# Sonar_Power_Schematic.net
KiCad netlist of a schematic drawn in EAGLE
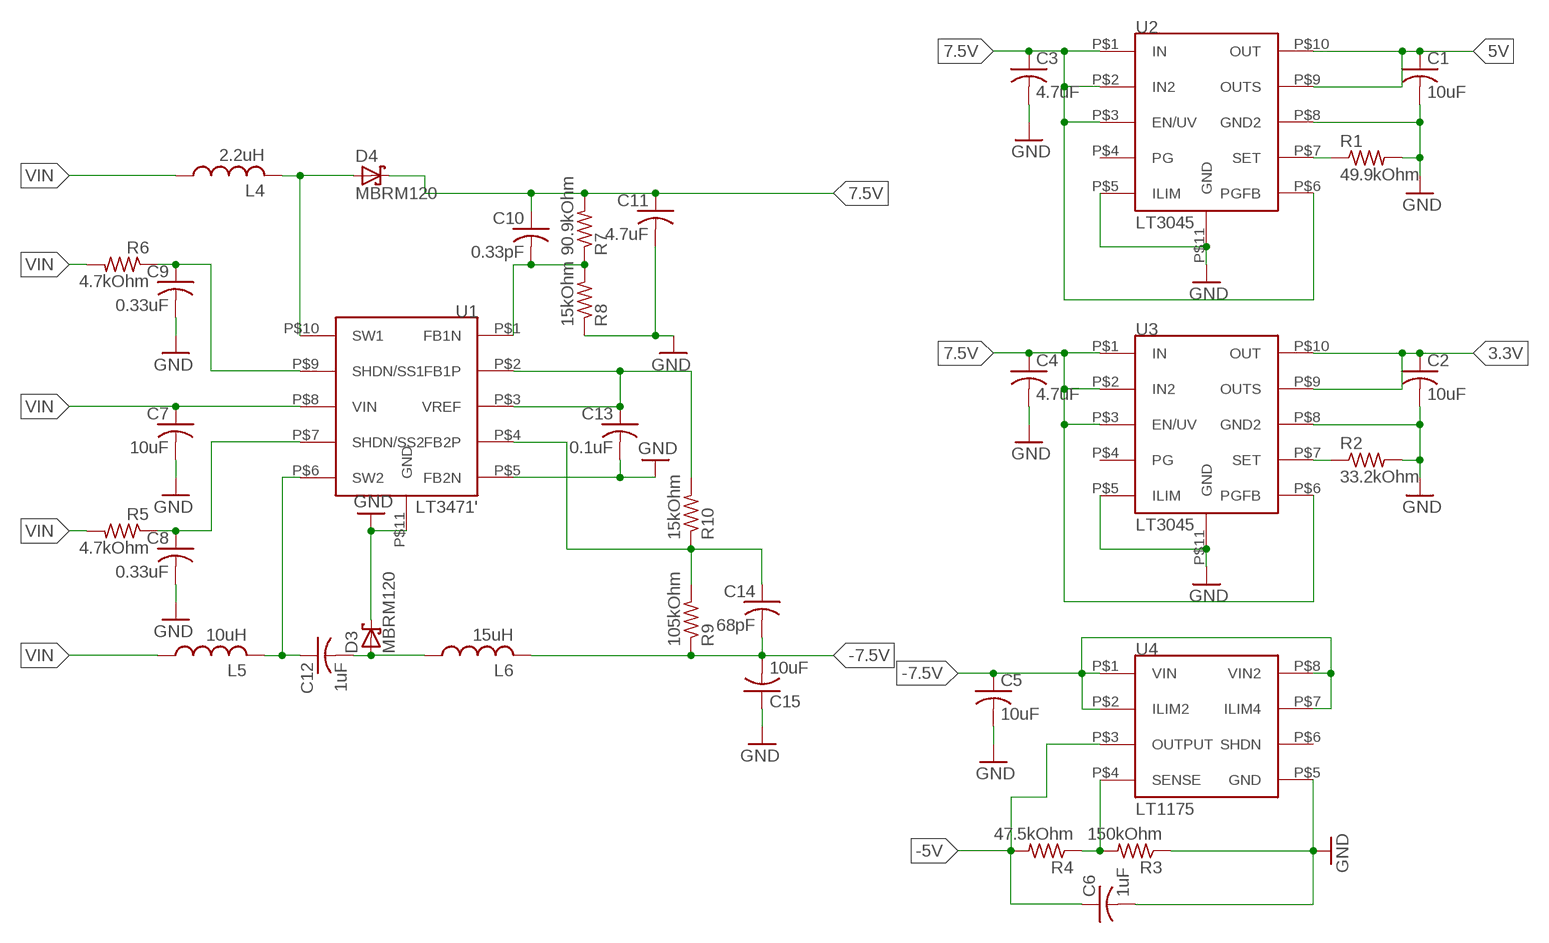
[diagram p0: schematic, sheet 1]

(export (version "E")
  (design (tool "Eeschema 10.0.6"))
  (components
    (comp (ref "C1")
      (value "10uF")
      (footprint "eagle-import:C1206K")
      (libsource (lib "eagle-import") (part "C-USC1206K"))
    )
    (comp (ref "C2")
      (value "10uF")
      (footprint "eagle-import:C1206K")
      (libsource (lib "eagle-import") (part "C-USC1206K"))
    )
    (comp (ref "C3")
      (value "4.7uF")
      (footprint "eagle-import:C0603")
      (libsource (lib "eagle-import") (part "C-USC0603"))
    )
    (comp (ref "C4")
      (value "4.7uF")
      (footprint "eagle-import:C0603")
      (libsource (lib "eagle-import") (part "C-USC0603"))
    )
    (comp (ref "C5")
      (value "10uF")
      (footprint "eagle-import:C0603")
      (libsource (lib "eagle-import") (part "C-USC0603"))
    )
    (comp (ref "C6")
      (value "1uF")
      (footprint "eagle-import:C0603")
      (libsource (lib "eagle-import") (part "C-USC0603"))
    )
    (comp (ref "C7")
      (value "10uF")
      (footprint "eagle-import:C0603")
      (libsource (lib "eagle-import") (part "C-USC0603"))
    )
    (comp (ref "C8")
      (value "0.33uF")
      (footprint "eagle-import:C0603")
      (libsource (lib "eagle-import") (part "C-USC0603"))
    )
    (comp (ref "C9")
      (value "0.33uF")
      (footprint "eagle-import:C0603")
      (libsource (lib "eagle-import") (part "C-USC0603"))
    )
    (comp (ref "C10")
      (value "0.33pF")
      (footprint "eagle-import:C0603")
      (libsource (lib "eagle-import") (part "C-USC0603"))
    )
    (comp (ref "C11")
      (value "4.7uF")
      (footprint "eagle-import:C0603")
      (libsource (lib "eagle-import") (part "C-USC0603"))
    )
    (comp (ref "C12")
      (value "1uF")
      (footprint "eagle-import:C0603")
      (libsource (lib "eagle-import") (part "C-USC0603"))
    )
    (comp (ref "C13")
      (value "0.1uF")
      (footprint "eagle-import:C0603")
      (libsource (lib "eagle-import") (part "C-USC0603"))
    )
    (comp (ref "C14")
      (value "68pF")
      (footprint "eagle-import:C0603")
      (libsource (lib "eagle-import") (part "C-USC0603"))
    )
    (comp (ref "C15")
      (value "10uF")
      (footprint "eagle-import:C0603")
      (libsource (lib "eagle-import") (part "C-USC0603"))
    )
    (comp (ref "D3")
      (value "MBRM120")
      (footprint "eagle-import:DO-216AA")
      (libsource (lib "eagle-import") (part "MBRM120"))
    )
    (comp (ref "D4")
      (value "MBRM120")
      (footprint "eagle-import:DO-216AA")
      (libsource (lib "eagle-import") (part "MBRM120"))
    )
    (comp (ref "L4")
      (value "2.2uH")
      (footprint "eagle-import:NS4.9X4.9")
      (libsource (lib "eagle-import") (part "LQH5BPN2R2N38L"))
    )
    (comp (ref "L5")
      (value "10uH")
      (footprint "eagle-import:NS5X5")
      (libsource (lib "eagle-import") (part "VLS5045EX-100M2"))
    )
    (comp (ref "L6")
      (value "15uH")
      (footprint "eagle-import:NS5X5")
      (libsource (lib "eagle-import") (part "VLS5045EX-150M-CA1"))
    )
    (comp (ref "R1")
      (value "49.9kOhm")
      (footprint "eagle-import:R0603")
      (libsource (lib "eagle-import") (part "R-US_R0603"))
    )
    (comp (ref "R2")
      (value "33.2kOhm")
      (footprint "eagle-import:R0603")
      (libsource (lib "eagle-import") (part "R-US_R0603"))
    )
    (comp (ref "R3")
      (value "150kOhm")
      (footprint "eagle-import:R0603")
      (libsource (lib "eagle-import") (part "R-US_R0603"))
    )
    (comp (ref "R4")
      (value "47.5kOhm")
      (footprint "eagle-import:R0603")
      (libsource (lib "eagle-import") (part "R-US_R0603"))
    )
    (comp (ref "R5")
      (value "4.7kOhm")
      (footprint "eagle-import:R0603")
      (libsource (lib "eagle-import") (part "R-US_R0603"))
    )
    (comp (ref "R6")
      (value "4.7kOhm")
      (footprint "eagle-import:R0603")
      (libsource (lib "eagle-import") (part "R-US_R0603"))
    )
    (comp (ref "R7")
      (value "90.9kOhm")
      (footprint "eagle-import:R0603")
      (libsource (lib "eagle-import") (part "R-US_R0603"))
    )
    (comp (ref "R8")
      (value "15kOhm")
      (footprint "eagle-import:R0603")
      (libsource (lib "eagle-import") (part "R-US_R0603"))
    )
    (comp (ref "R9")
      (value "105kOhm")
      (footprint "eagle-import:R0603")
      (libsource (lib "eagle-import") (part "R-US_R0603"))
    )
    (comp (ref "R10")
      (value "15kOhm")
      (footprint "eagle-import:R0603")
      (libsource (lib "eagle-import") (part "R-US_R0603"))
    )
    (comp (ref "U1")
      (value "LT3471'")
      (footprint "eagle-import:10-WFDFN")
      (libsource (lib "eagle-import") (part "LT3471'"))
    )
    (comp (ref "U2")
      (value "LT3045")
      (footprint "eagle-import:10-WFDFN")
      (libsource (lib "eagle-import") (part "LT3045"))
    )
    (comp (ref "U3")
      (value "LT3045")
      (footprint "eagle-import:10-WFDFN")
      (libsource (lib "eagle-import") (part "LT3045"))
    )
    (comp (ref "U4")
      (value "LT1175")
      (footprint "eagle-import:8-SOIC")
      (libsource (lib "eagle-import") (part "LT1175"))
    )
  )
  (nets
    (net (code "1") (name "-5V") (class "Default")
      (node (ref "C6") (pin "1") (pinfunction "1_1") (pintype "passive"))
      (node (ref "R4") (pin "2") (pinfunction "2_2") (pintype "passive"))
      (node (ref "U4") (pin "P$3") (pinfunction "OUTPUT_P$3") (pintype "bidirectional"))
    )
    (net (code "2") (name "-7.5V") (class "Default")
      (node (ref "C14") (pin "2") (pinfunction "2_2") (pintype "passive"))
      (node (ref "C15") (pin "2") (pinfunction "2_2") (pintype "passive"))
      (node (ref "C5") (pin "1") (pinfunction "1_1") (pintype "passive"))
      (node (ref "L6") (pin "P$2") (pinfunction "2_P$2") (pintype "passive"))
      (node (ref "R9") (pin "1") (pinfunction "1_1") (pintype "passive"))
      (node (ref "U4") (pin "P$1") (pinfunction "VIN_P$1") (pintype "power_in"))
      (node (ref "U4") (pin "P$2") (pinfunction "ILIM2_P$2") (pintype "bidirectional"))
      (node (ref "U4") (pin "P$7") (pinfunction "ILIM4_P$7") (pintype "bidirectional"))
      (node (ref "U4") (pin "P$8") (pinfunction "VIN2_P$8") (pintype "power_in"))
    )
    (net (code "3") (name "3.3V") (class "Default")
      (node (ref "C2") (pin "1") (pinfunction "1_1") (pintype "passive"))
      (node (ref "U3") (pin "P$10") (pinfunction "OUT_P$10") (pintype "bidirectional"))
      (node (ref "U3") (pin "P$9") (pinfunction "OUTS_P$9") (pintype "bidirectional"))
    )
    (net (code "4") (name "5V") (class "Default")
      (node (ref "C1") (pin "1") (pinfunction "1_1") (pintype "passive"))
      (node (ref "U2") (pin "P$10") (pinfunction "OUT_P$10") (pintype "bidirectional"))
      (node (ref "U2") (pin "P$9") (pinfunction "OUTS_P$9") (pintype "bidirectional"))
    )
    (net (code "5") (name "7.5V") (class "Default")
      (node (ref "C10") (pin "1") (pinfunction "1_1") (pintype "passive"))
      (node (ref "C11") (pin "1") (pinfunction "1_1") (pintype "passive"))
      (node (ref "C3") (pin "1") (pinfunction "1_1") (pintype "passive"))
      (node (ref "C4") (pin "1") (pinfunction "1_1") (pintype "passive"))
      (node (ref "D4") (pin "P$1") (pinfunction "C_P$1") (pintype "passive"))
      (node (ref "R7") (pin "2") (pinfunction "2_2") (pintype "passive"))
      (node (ref "U2") (pin "P$1") (pinfunction "IN_P$1") (pintype "power_in"))
      (node (ref "U2") (pin "P$2") (pinfunction "IN2_P$2") (pintype "power_in"))
      (node (ref "U2") (pin "P$3") (pinfunction "EN/UV_P$3") (pintype "bidirectional"))
      (node (ref "U2") (pin "P$6") (pinfunction "PGFB_P$6") (pintype "bidirectional"))
      (node (ref "U3") (pin "P$1") (pinfunction "IN_P$1") (pintype "power_in"))
      (node (ref "U3") (pin "P$2") (pinfunction "IN2_P$2") (pintype "power_in"))
      (node (ref "U3") (pin "P$3") (pinfunction "EN/UV_P$3") (pintype "bidirectional"))
      (node (ref "U3") (pin "P$6") (pinfunction "PGFB_P$6") (pintype "bidirectional"))
    )
    (net (code "6") (name "GND") (class "Default")
      (node (ref "C1") (pin "2") (pinfunction "2_2") (pintype "passive"))
      (node (ref "C11") (pin "2") (pinfunction "2_2") (pintype "passive"))
      (node (ref "C13") (pin "2") (pinfunction "2_2") (pintype "passive"))
      (node (ref "C15") (pin "1") (pinfunction "1_1") (pintype "passive"))
      (node (ref "C2") (pin "2") (pinfunction "2_2") (pintype "passive"))
      (node (ref "C3") (pin "2") (pinfunction "2_2") (pintype "passive"))
      (node (ref "C4") (pin "2") (pinfunction "2_2") (pintype "passive"))
      (node (ref "C5") (pin "2") (pinfunction "2_2") (pintype "passive"))
      (node (ref "C6") (pin "2") (pinfunction "2_2") (pintype "passive"))
      (node (ref "C7") (pin "2") (pinfunction "2_2") (pintype "passive"))
      (node (ref "C8") (pin "2") (pinfunction "2_2") (pintype "passive"))
      (node (ref "C9") (pin "2") (pinfunction "2_2") (pintype "passive"))
      (node (ref "D3") (pin "P$1") (pinfunction "C_P$1") (pintype "passive"))
      (node (ref "R1") (pin "2") (pinfunction "2_2") (pintype "passive"))
      (node (ref "R2") (pin "2") (pinfunction "2_2") (pintype "passive"))
      (node (ref "R3") (pin "1") (pinfunction "1_1") (pintype "passive"))
      (node (ref "R8") (pin "1") (pinfunction "1_1") (pintype "passive"))
      (node (ref "U1") (pin "P$11") (pinfunction "GND_P$11") (pintype "power_in"))
      (node (ref "U1") (pin "P$5") (pinfunction "FB2N_P$5") (pintype "bidirectional"))
      (node (ref "U2") (pin "P$11") (pinfunction "GND_P$11") (pintype "power_in"))
      (node (ref "U2") (pin "P$5") (pinfunction "ILIM_P$5") (pintype "bidirectional"))
      (node (ref "U2") (pin "P$8") (pinfunction "GND2_P$8") (pintype "power_in"))
      (node (ref "U3") (pin "P$11") (pinfunction "GND_P$11") (pintype "power_in"))
      (node (ref "U3") (pin "P$5") (pinfunction "ILIM_P$5") (pintype "bidirectional"))
      (node (ref "U3") (pin "P$8") (pinfunction "GND2_P$8") (pintype "power_in"))
      (node (ref "U4") (pin "P$5") (pinfunction "GND_P$5") (pintype "power_in"))
    )
    (net (code "7") (name "Net-(D3-A)") (class "Default")
      (node (ref "C12") (pin "2") (pinfunction "2_2") (pintype "passive"))
      (node (ref "D3") (pin "P$2") (pinfunction "A_P$2") (pintype "passive"))
      (node (ref "L6") (pin "P$1") (pinfunction "1_P$1") (pintype "passive"))
    )
    (net (code "8") (name "Net-(D4-A)") (class "Default")
      (node (ref "D4") (pin "P$2") (pinfunction "A_P$2") (pintype "passive"))
      (node (ref "L4") (pin "P$2") (pinfunction "2_P$2") (pintype "passive"))
      (node (ref "U1") (pin "P$10") (pinfunction "SW1_P$10") (pintype "bidirectional"))
    )
    (net (code "9") (name "Net-(L5-2)") (class "Default")
      (node (ref "C12") (pin "1") (pinfunction "1_1") (pintype "passive"))
      (node (ref "L5") (pin "P$2") (pinfunction "2_P$2") (pintype "passive"))
      (node (ref "U1") (pin "P$6") (pinfunction "SW2_P$6") (pintype "bidirectional"))
    )
    (net (code "10") (name "Net-(U1-FB1N)") (class "Default")
      (node (ref "C10") (pin "2") (pinfunction "2_2") (pintype "passive"))
      (node (ref "R7") (pin "1") (pinfunction "1_1") (pintype "passive"))
      (node (ref "R8") (pin "2") (pinfunction "2_2") (pintype "passive"))
      (node (ref "U1") (pin "P$1") (pinfunction "FB1N_P$1") (pintype "bidirectional"))
    )
    (net (code "11") (name "Net-(U1-FB1P)") (class "Default")
      (node (ref "C13") (pin "1") (pinfunction "1_1") (pintype "passive"))
      (node (ref "R10") (pin "2") (pinfunction "2_2") (pintype "passive"))
      (node (ref "U1") (pin "P$2") (pinfunction "FB1P_P$2") (pintype "bidirectional"))
      (node (ref "U1") (pin "P$3") (pinfunction "VREF_P$3") (pintype "power_in"))
    )
    (net (code "12") (name "Net-(U1-FB2P)") (class "Default")
      (node (ref "C14") (pin "1") (pinfunction "1_1") (pintype "passive"))
      (node (ref "R10") (pin "1") (pinfunction "1_1") (pintype "passive"))
      (node (ref "R9") (pin "2") (pinfunction "2_2") (pintype "passive"))
      (node (ref "U1") (pin "P$4") (pinfunction "FB2P_P$4") (pintype "bidirectional"))
    )
    (net (code "13") (name "Net-(U1-SHDN{slash}SS1)") (class "Default")
      (node (ref "C9") (pin "1") (pinfunction "1_1") (pintype "passive"))
      (node (ref "R6") (pin "1") (pinfunction "1_1") (pintype "passive"))
      (node (ref "U1") (pin "P$9") (pinfunction "SHDN/SS1_P$9") (pintype "bidirectional"))
    )
    (net (code "14") (name "Net-(U1-SHDN{slash}SS2)") (class "Default")
      (node (ref "C8") (pin "1") (pinfunction "1_1") (pintype "passive"))
      (node (ref "R5") (pin "1") (pinfunction "1_1") (pintype "passive"))
      (node (ref "U1") (pin "P$7") (pinfunction "SHDN/SS2_P$7") (pintype "bidirectional"))
    )
    (net (code "15") (name "Net-(U2-SET)") (class "Default")
      (node (ref "R1") (pin "1") (pinfunction "1_1") (pintype "passive"))
      (node (ref "U2") (pin "P$7") (pinfunction "SET_P$7") (pintype "bidirectional"))
    )
    (net (code "16") (name "Net-(U3-SET)") (class "Default")
      (node (ref "R2") (pin "1") (pinfunction "1_1") (pintype "passive"))
      (node (ref "U3") (pin "P$7") (pinfunction "SET_P$7") (pintype "bidirectional"))
    )
    (net (code "17") (name "Net-(U4-SENSE)") (class "Default")
      (node (ref "R3") (pin "2") (pinfunction "2_2") (pintype "passive"))
      (node (ref "R4") (pin "1") (pinfunction "1_1") (pintype "passive"))
      (node (ref "U4") (pin "P$4") (pinfunction "SENSE_P$4") (pintype "bidirectional"))
    )
    (net (code "18") (name "VIN") (class "Default")
      (node (ref "C7") (pin "1") (pinfunction "1_1") (pintype "passive"))
      (node (ref "L4") (pin "P$1") (pinfunction "1_P$1") (pintype "passive"))
      (node (ref "L5") (pin "P$1") (pinfunction "1_P$1") (pintype "passive"))
      (node (ref "R5") (pin "2") (pinfunction "2_2") (pintype "passive"))
      (node (ref "R6") (pin "2") (pinfunction "2_2") (pintype "passive"))
      (node (ref "U1") (pin "P$8") (pinfunction "VIN_P$8") (pintype "power_in"))
    )
    (net (code "19") (name "unconnected-(U2-PG-PadP$4)") (class "Default")
      (node (ref "U2") (pin "P$4") (pinfunction "PG_P$4") (pintype "bidirectional"))
    )
    (net (code "20") (name "unconnected-(U3-PG-PadP$4)") (class "Default")
      (node (ref "U3") (pin "P$4") (pinfunction "PG_P$4") (pintype "bidirectional"))
    )
    (net (code "21") (name "unconnected-(U4-SHDN-PadP$6)") (class "Default")
      (node (ref "U4") (pin "P$6") (pinfunction "SHDN_P$6") (pintype "bidirectional"))
    )
  )
)
